# mcu.net
KiCad netlist of a schematic drawn in Altium Designer
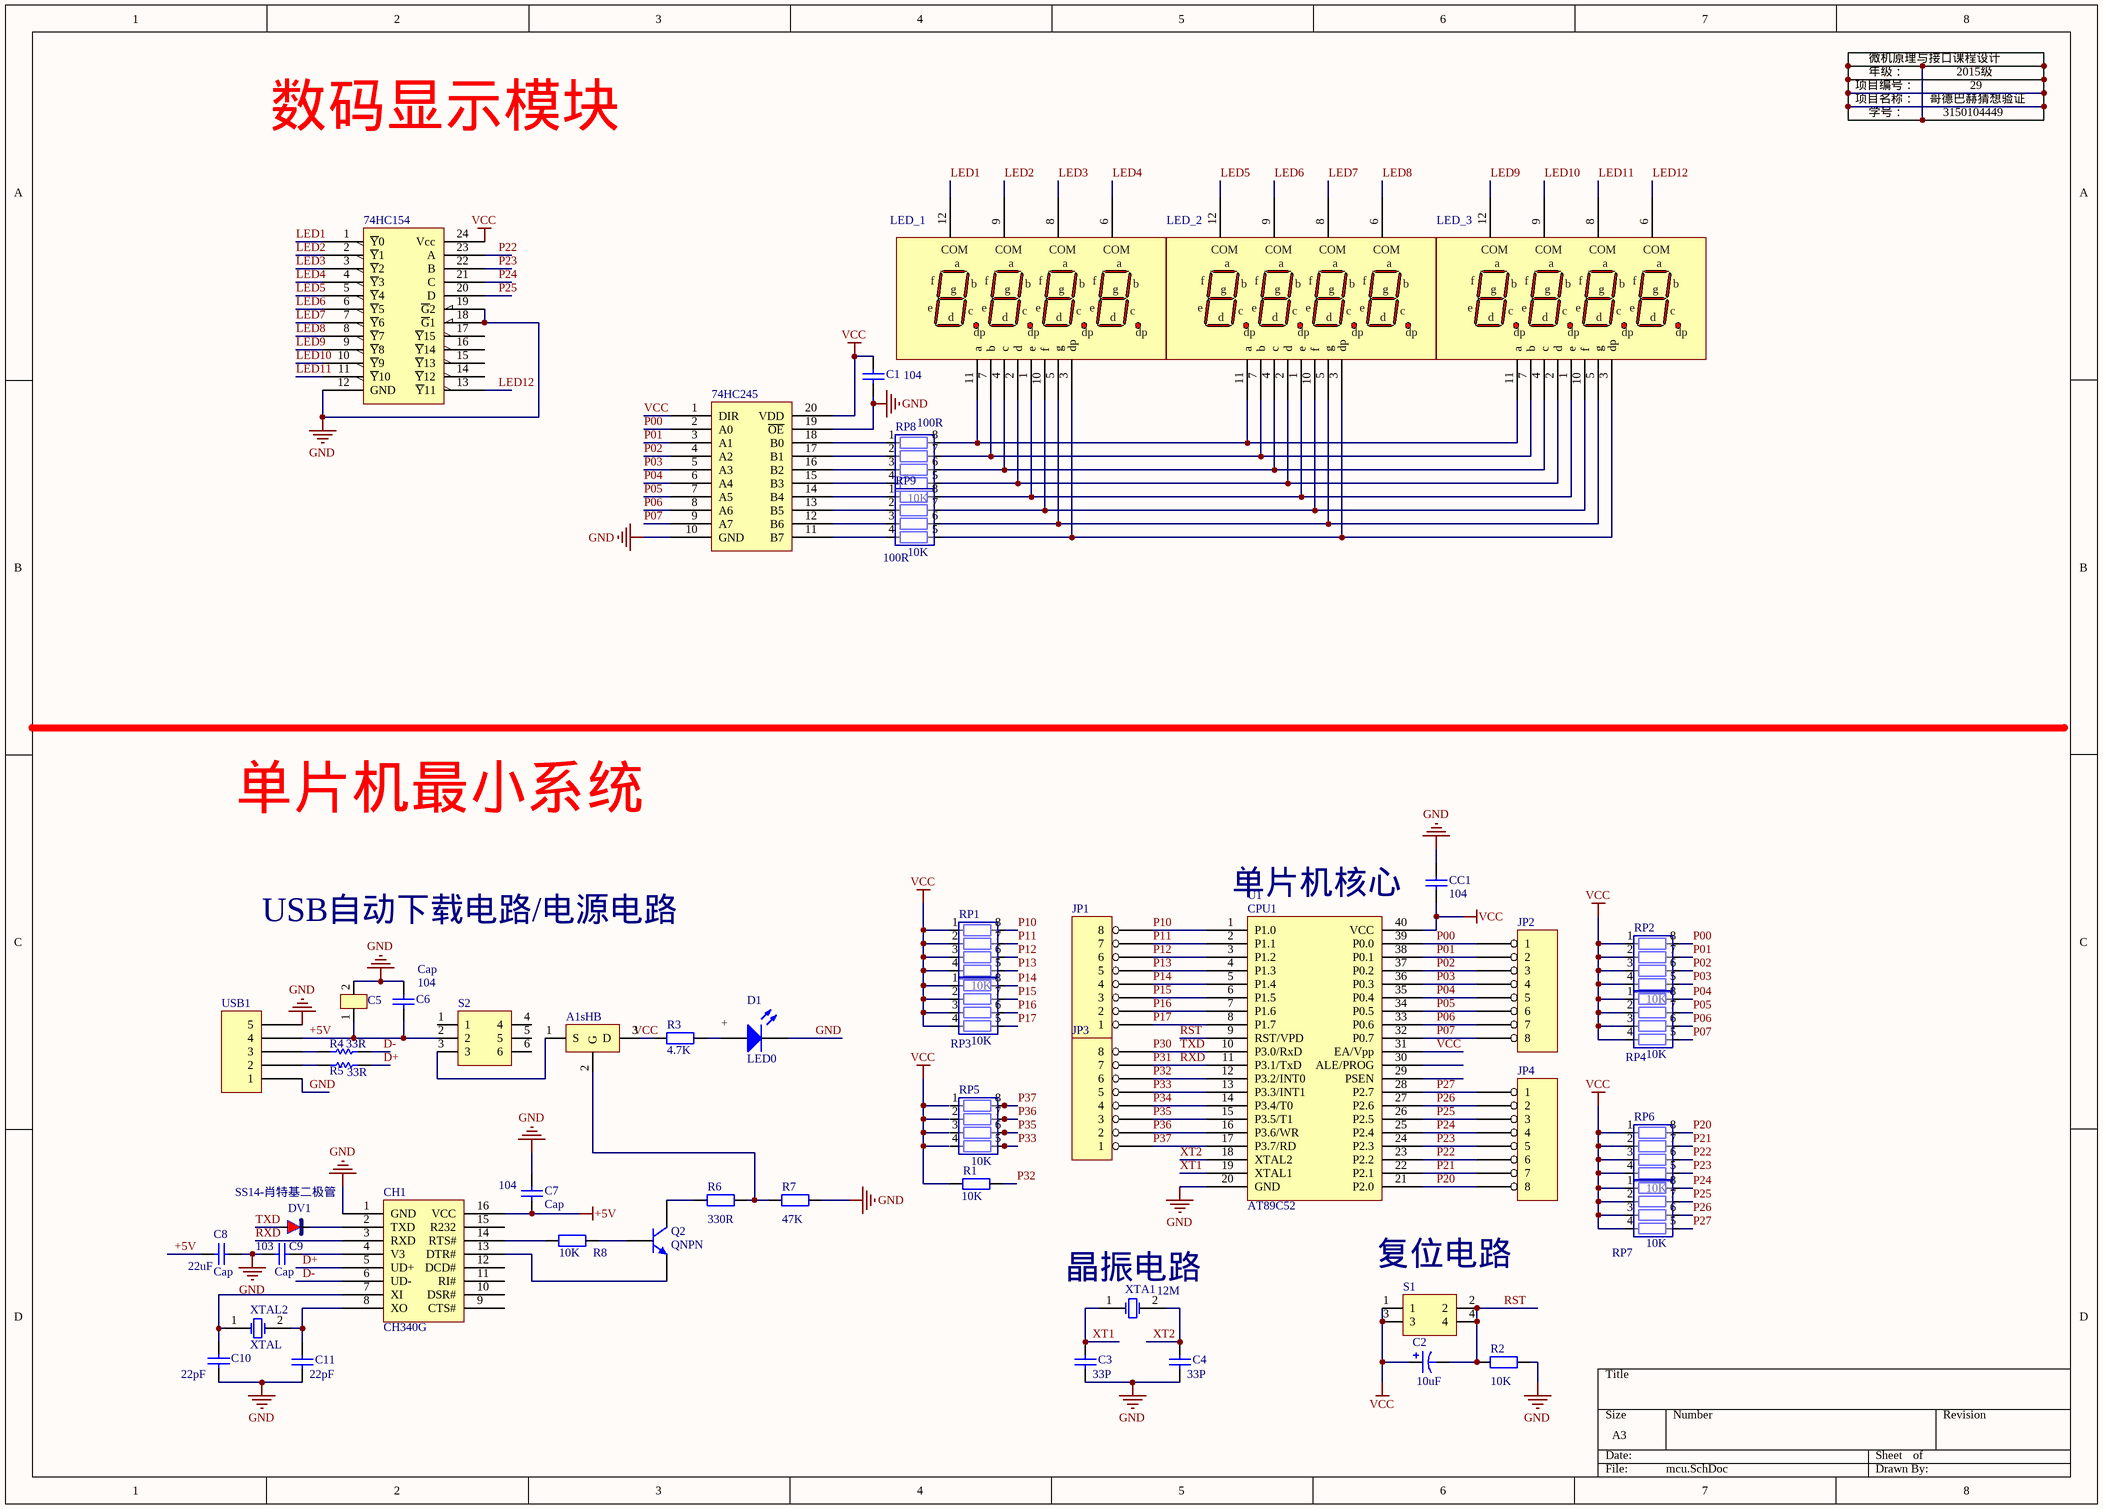
[diagram p0: mcu.SchDoc]

(export (version "E")
  (design (tool "Eeschema 10.0.6"))
  (components
    (comp (ref "74HC154")
      (value "74HC154")
      (footprint "mcu_PcbLib1:SOP24-74HC154D")
      (fields (field (name "PUBLISHER") "Altium Limited"))
      (libsource (lib "mcu_Schlib1") (part "74HC154"))
    )
    (comp (ref "74HC245")
      (value "74HC245")
      (footprint "mcu_PcbLib1:SOP20-74HC245")
      (fields (field (name "PUBLISHER") "Altium Limited"))
      (libsource (lib "mcu_Schlib1") (part "74HC245"))
    )
    (comp (ref "A1sHB")
      (value "A1sHB")
      (footprint "mcu_PcbLib1:A1sHB")
      (fields (field (name "PUBLISHER") "Altium Limited"))
      (libsource (lib "mcu_Schlib1") (part "A1sHB"))
    )
    (comp (ref "C1")
      (value "104")
      (footprint "RAD-0.3")
      (description "Capacitor")
      (fields (field (name "Comment") "Cap") (field (name "PUBLISHER") "Altium Limited"))
      (libsource (lib "Miscellaneous Devices") (part "Cap"))
    )
    (comp (ref "C2")
      (value "10uF")
      (footprint "RB7.6-15")
      (description "Polarized Capacitor (Radial)")
      (fields (field (name "Comment") "Cap Pol1") (field (name "PUBLISHER") "Altium Limited"))
      (libsource (lib "Miscellaneous Devices") (part "Cap Pol1"))
    )
    (comp (ref "C3")
      (value "33P")
      (footprint "RAD-0.3")
      (description "Capacitor")
      (fields (field (name "Comment") "Cap") (field (name "PUBLISHER") "Altium Limited"))
      (libsource (lib "Miscellaneous Devices") (part "Cap"))
    )
    (comp (ref "C4")
      (value "33P")
      (footprint "RAD-0.3")
      (description "Capacitor")
      (fields (field (name "Comment") "Cap") (field (name "PUBLISHER") "Altium Limited"))
      (libsource (lib "Miscellaneous Devices") (part "Cap"))
    )
    (comp (ref "C5")
      (value "470uF")
      (footprint "mcu_PcbLib1:C5-CP1")
      (description "High Conductance Fast Diode")
      (fields (field (name "PUBLISHER") "Altium Limited"))
      (libsource (lib "mcu_Schlib1") (part "C5"))
    )
    (comp (ref "C6")
      (value "Cap")
      (footprint "RAD-0.3")
      (description "Capacitor")
      (fields (field (name "ALTIUM_VALUE") "104") (field (name "PUBLISHER") "Altium Limited"))
      (libsource (lib "Miscellaneous Devices") (part "Cap"))
    )
    (comp (ref "C7")
      (value "Cap")
      (footprint "RAD-0.3")
      (description "Capacitor")
      (fields (field (name "ALTIUM_VALUE") "104") (field (name "PUBLISHER") "Altium Limited"))
      (libsource (lib "Miscellaneous Devices") (part "Cap"))
    )
    (comp (ref "C8")
      (value "Cap")
      (footprint "RAD-0.3")
      (description "Capacitor")
      (fields (field (name "ALTIUM_VALUE") "22uF") (field (name "PUBLISHER") "Altium Limited"))
      (libsource (lib "Miscellaneous Devices") (part "Cap"))
    )
    (comp (ref "C9")
      (value "Cap")
      (footprint "RAD-0.3")
      (description "Capacitor")
      (fields (field (name "ALTIUM_VALUE") "103") (field (name "PUBLISHER") "Altium Limited"))
      (libsource (lib "Miscellaneous Devices") (part "Cap"))
    )
    (comp (ref "C10")
      (value "22pF")
      (footprint "RAD-0.3")
      (description "Capacitor")
      (fields (field (name "Comment") "Cap") (field (name "PUBLISHER") "Altium Limited"))
      (libsource (lib "Miscellaneous Devices") (part "Cap"))
    )
    (comp (ref "C11")
      (value "22pF")
      (footprint "RAD-0.3")
      (description "Capacitor")
      (fields (field (name "Comment") "Cap") (field (name "PUBLISHER") "Altium Limited"))
      (libsource (lib "Miscellaneous Devices") (part "Cap"))
    )
    (comp (ref "CC1")
      (value "104")
      (footprint "RAD-0.3")
      (description "Capacitor")
      (fields (field (name "Comment") "Cap") (field (name "PUBLISHER") "Altium Limited"))
      (libsource (lib "Miscellaneous Devices") (part "Cap"))
    )
    (comp (ref "CH1")
      (value "CH340G")
      (footprint "mcu_PcbLib1:SOP16-CH1-CH340G")
      (description "CH1")
      (fields (field (name "PUBLISHER") "Altium Limited"))
      (libsource (lib "mcu_Schlib1") (part "CH1"))
    )
    (comp (ref "D1")
      (value "LED0")
      (footprint "LED-0")
      (description "Typical INFRARED GaAs LED")
      (fields (field (name "PUBLISHER") "Altium Limited"))
      (libsource (lib "Miscellaneous Devices") (part "LED0"))
    )
    (comp (ref "DV1")
      (value "SS14-肖特基二极管")
      (footprint "mcu_PcbLib1:DV1-SS14")
      (description "DV1")
      (fields (field (name "PUBLISHER") "Altium Limited"))
      (libsource (lib "mcu_Schlib1") (part "DV1"))
    )
    (comp (ref "JP1")
      (value "JP1")
      (footprint "mcu_PcbLib1:JP")
      (fields (field (name "PUBLISHER") "Altium Limited"))
      (libsource (lib "") (part "JP1_1"))
    )
    (comp (ref "JP2")
      (value "JP1")
      (footprint "mcu_PcbLib1:JP")
      (fields (field (name "PUBLISHER") "Altium Limited"))
      (libsource (lib "mcu_Schlib1") (part "JP1"))
    )
    (comp (ref "JP3")
      (value "JP1")
      (footprint "mcu_PcbLib1:JP")
      (fields (field (name "PUBLISHER") "Altium Limited"))
      (libsource (lib "") (part "JP1_1"))
    )
    (comp (ref "JP4")
      (value "JP1")
      (footprint "mcu_PcbLib1:JP")
      (fields (field (name "PUBLISHER") "Altium Limited"))
      (libsource (lib "mcu_Schlib1") (part "JP1"))
    )
    (comp (ref "LED_1")
      (value "LED_12")
      (footprint "mcu_PcbLib1:LED_12")
      (fields (field (name "PUBLISHER") "Altium Limited"))
      (libsource (lib "mcu_Schlib1") (part "LED_12"))
    )
    (comp (ref "LED_2")
      (value "LED_12")
      (footprint "mcu_PcbLib1:LED_12")
      (fields (field (name "PUBLISHER") "Altium Limited"))
      (libsource (lib "mcu_Schlib1") (part "LED_12"))
    )
    (comp (ref "LED_3")
      (value "LED_12")
      (footprint "mcu_PcbLib1:LED_12")
      (fields (field (name "PUBLISHER") "Altium Limited"))
      (libsource (lib "mcu_Schlib1") (part "LED_12"))
    )
    (comp (ref "Q2")
      (value "QNPN")
      (footprint "SOT-23B")
      (description "NPN Bipolar Transistor")
      (fields (field (name "PUBLISHER") "Altium Limited"))
      (libsource (lib "Miscellaneous Devices") (part "QNPN"))
    )
    (comp (ref "R1")
      (value "10K")
      (footprint "AXIAL-0.4")
      (description "Resistor")
      (fields (field (name "Comment") "Res2") (field (name "PUBLISHER") "Altium Limited"))
      (libsource (lib "Miscellaneous Devices") (part "Res2"))
    )
    (comp (ref "R2")
      (value "10K")
      (footprint "AXIAL-0.4")
      (description "Resistor")
      (fields (field (name "Comment") "Res2") (field (name "PUBLISHER") "Altium Limited"))
      (libsource (lib "Miscellaneous Devices") (part "Res2"))
    )
    (comp (ref "R3")
      (value "4.7K")
      (footprint "AXIAL-0.4")
      (description "Resistor")
      (fields (field (name "Comment") "Res2") (field (name "PUBLISHER") "Altium Limited"))
      (libsource (lib "Miscellaneous Devices") (part "Res2"))
    )
    (comp (ref "R4")
      (value "33R")
      (footprint "AXIAL-0.3")
      (description "Resistor")
      (fields (field (name "PUBLISHER") "Altium Limited"))
      (libsource (lib "Miscellaneous Devices") (part "Res1"))
    )
    (comp (ref "R5")
      (value "33R")
      (footprint "AXIAL-0.3")
      (description "Resistor")
      (fields (field (name "PUBLISHER") "Altium Limited"))
      (libsource (lib "Miscellaneous Devices") (part "Res1"))
    )
    (comp (ref "R6")
      (value "330R")
      (footprint "AXIAL-0.4")
      (description "Resistor")
      (fields (field (name "Comment") "Res2") (field (name "PUBLISHER") "Altium Limited"))
      (libsource (lib "Miscellaneous Devices") (part "Res2"))
    )
    (comp (ref "R7")
      (value "47K")
      (footprint "AXIAL-0.4")
      (description "Resistor")
      (fields (field (name "Comment") "Res2") (field (name "PUBLISHER") "Altium Limited"))
      (libsource (lib "Miscellaneous Devices") (part "Res2"))
    )
    (comp (ref "R8")
      (value "10K")
      (footprint "AXIAL-0.4")
      (description "Resistor")
      (fields (field (name "Comment") "Res2") (field (name "PUBLISHER") "Altium Limited"))
      (libsource (lib "Miscellaneous Devices") (part "Res2"))
    )
    (comp (ref "RP1")
      (value "RP1")
      (footprint "mcu_PcbLib1:RP-8P4R-0603")
      (fields (field (name "PUBLISHER") "Altium Limited"))
      (libsource (lib "mcu_Schlib1") (part "RP1"))
    )
    (comp (ref "RP2")
      (value "RP1")
      (footprint "mcu_PcbLib1:RP-8P4R-0603")
      (fields (field (name "PUBLISHER") "Altium Limited"))
      (libsource (lib "mcu_Schlib1") (part "RP1"))
    )
    (comp (ref "RP3")
      (value "RP1")
      (footprint "mcu_PcbLib1:RP-8P4R-0603")
      (fields (field (name "PUBLISHER") "Altium Limited"))
      (libsource (lib "mcu_Schlib1") (part "RP1"))
    )
    (comp (ref "RP4")
      (value "RP1")
      (footprint "mcu_PcbLib1:RP-8P4R-0603")
      (fields (field (name "PUBLISHER") "Altium Limited"))
      (libsource (lib "mcu_Schlib1") (part "RP1"))
    )
    (comp (ref "RP5")
      (value "RP1")
      (footprint "mcu_PcbLib1:RP-8P4R-0603")
      (fields (field (name "PUBLISHER") "Altium Limited"))
      (libsource (lib "mcu_Schlib1") (part "RP1"))
    )
    (comp (ref "RP6")
      (value "RP1")
      (footprint "mcu_PcbLib1:RP-8P4R-0603")
      (fields (field (name "PUBLISHER") "Altium Limited"))
      (libsource (lib "mcu_Schlib1") (part "RP1"))
    )
    (comp (ref "RP7")
      (value "RP1")
      (footprint "mcu_PcbLib1:RP-8P4R-0603")
      (fields (field (name "PUBLISHER") "Altium Limited"))
      (libsource (lib "mcu_Schlib1") (part "RP1"))
    )
    (comp (ref "RP8")
      (value "RP1")
      (footprint "mcu_PcbLib1:RP-8P4R-0603")
      (fields (field (name "PUBLISHER") "Altium Limited"))
      (libsource (lib "mcu_Schlib1") (part "RP1"))
    )
    (comp (ref "RP9")
      (value "RP1")
      (footprint "mcu_PcbLib1:RP-8P4R-0603")
      (fields (field (name "PUBLISHER") "Altium Limited"))
      (libsource (lib "mcu_Schlib1") (part "RP1"))
    )
    (comp (ref "S1")
      (value "S1")
      (footprint "mcu_PcbLib1:DIP4-S1")
      (fields (field (name "PUBLISHER") "Altium Limited"))
      (libsource (lib "mcu_Schlib1") (part "S1"))
    )
    (comp (ref "S2")
      (value "S2")
      (footprint "mcu_PcbLib1:DIP6-S2")
      (fields (field (name "PUBLISHER") "Altium Limited"))
      (libsource (lib "mcu_Schlib1") (part "S2"))
    )
    (comp (ref "U1")
      (value "AT89C52")
      (footprint "mcu_PcbLib1:CPU_DIP40")
      (fields (field (name "PUBLISHER") "Altium Limited"))
      (libsource (lib "mcu_Schlib1") (part "AT89C52"))
    )
    (comp (ref "USB1")
      (value "USB1")
      (footprint "mcu_PcbLib1:USB1")
      (fields (field (name "PUBLISHER") "Altium Limited"))
      (libsource (lib "mcu_Schlib1") (part "USB1"))
    )
    (comp (ref "XTA1")
      (value "12M")
      (footprint "R38")
      (description "Crystal Oscillator")
      (fields (field (name "PUBLISHER") "Altium Limited"))
      (libsource (lib "Miscellaneous Devices") (part "XTAL"))
    )
    (comp (ref "XTAL2")
      (value "XTAL")
      (footprint "R38")
      (description "Crystal Oscillator")
      (fields (field (name "PUBLISHER") "Altium Limited"))
      (libsource (lib "Miscellaneous Devices") (part "XTAL"))
    )
  )
  (nets
    (net (code "1") (name "+5V") (class "Default")
      (node (ref "C5") (pin "1") (pinfunction "1_1") (pintype "passive"))
      (node (ref "C6") (pin "1") (pinfunction "1_1") (pintype "passive"))
      (node (ref "C7") (pin "1") (pinfunction "1_1") (pintype "passive"))
      (node (ref "C8") (pin "1") (pinfunction "1_1") (pintype "passive"))
      (node (ref "CH1") (pin "16") (pinfunction "VCC_16") (pintype "passive"))
      (node (ref "S2") (pin "2") (pinfunction "2_2") (pintype "passive"))
      (node (ref "USB1") (pin "4") (pinfunction "4_4") (pintype "passive"))
    )
    (net (code "2") (name "/D+") (class "Default")
      (node (ref "CH1") (pin "5") (pinfunction "UD+_5") (pintype "passive"))
      (node (ref "R5") (pin "2") (pinfunction "2_2") (pintype "passive"))
    )
    (net (code "3") (name "/D-") (class "Default")
      (node (ref "CH1") (pin "6") (pinfunction "UD-_6") (pintype "passive"))
      (node (ref "R4") (pin "2") (pinfunction "2_2") (pintype "passive"))
    )
    (net (code "4") (name "/LED1") (class "Default")
      (node (ref "74HC154") (pin "1") (pinfunction "~{Y}0_1") (pintype "passive"))
      (node (ref "LED_1") (pin "12") (pinfunction "COM_12") (pintype "passive"))
    )
    (net (code "5") (name "/LED2") (class "Default")
      (node (ref "74HC154") (pin "2") (pinfunction "~{Y}1_2") (pintype "passive"))
      (node (ref "LED_1") (pin "9") (pinfunction "COM_9") (pintype "passive"))
    )
    (net (code "6") (name "/LED3") (class "Default")
      (node (ref "74HC154") (pin "3") (pinfunction "~{Y}2_3") (pintype "passive"))
      (node (ref "LED_1") (pin "8") (pinfunction "COM_8") (pintype "passive"))
    )
    (net (code "7") (name "/LED4") (class "Default")
      (node (ref "74HC154") (pin "4") (pinfunction "~{Y}3_4") (pintype "passive"))
      (node (ref "LED_1") (pin "6") (pinfunction "COM_6") (pintype "passive"))
    )
    (net (code "8") (name "/LED5") (class "Default")
      (node (ref "74HC154") (pin "5") (pinfunction "~{Y}4_5") (pintype "passive"))
      (node (ref "LED_2") (pin "12") (pinfunction "COM_12") (pintype "passive"))
    )
    (net (code "9") (name "/LED6") (class "Default")
      (node (ref "74HC154") (pin "6") (pinfunction "~{Y}5_6") (pintype "passive"))
      (node (ref "LED_2") (pin "9") (pinfunction "COM_9") (pintype "passive"))
    )
    (net (code "10") (name "/LED7") (class "Default")
      (node (ref "74HC154") (pin "7") (pinfunction "~{Y}6_7") (pintype "passive"))
      (node (ref "LED_2") (pin "8") (pinfunction "COM_8") (pintype "passive"))
    )
    (net (code "11") (name "/LED8") (class "Default")
      (node (ref "74HC154") (pin "8") (pinfunction "~{Y}7_8") (pintype "passive"))
      (node (ref "LED_2") (pin "6") (pinfunction "COM_6") (pintype "passive"))
    )
    (net (code "12") (name "/LED9") (class "Default")
      (node (ref "74HC154") (pin "9") (pinfunction "~{Y}8_9") (pintype "passive"))
      (node (ref "LED_3") (pin "12") (pinfunction "COM_12") (pintype "passive"))
    )
    (net (code "13") (name "/LED10") (class "Default")
      (node (ref "74HC154") (pin "10") (pinfunction "~{Y}9_10") (pintype "passive"))
      (node (ref "LED_3") (pin "9") (pinfunction "COM_9") (pintype "passive"))
    )
    (net (code "14") (name "/LED11") (class "Default")
      (node (ref "74HC154") (pin "11") (pinfunction "~{Y}10_11") (pintype "passive"))
      (node (ref "LED_3") (pin "8") (pinfunction "COM_8") (pintype "passive"))
    )
    (net (code "15") (name "/LED12") (class "Default")
      (node (ref "74HC154") (pin "13") (pinfunction "~{Y}11_13") (pintype "passive"))
      (node (ref "LED_3") (pin "6") (pinfunction "COM_6") (pintype "passive"))
    )
    (net (code "16") (name "/P00") (class "Default")
      (node (ref "74HC245") (pin "2") (pinfunction "A0_2") (pintype "passive"))
      (node (ref "JP2") (pin "1") (pinfunction "1_1") (pintype "passive"))
      (node (ref "RP2") (pin "8") (pinfunction "8_8") (pintype "passive"))
      (node (ref "U1") (pin "39") (pinfunction "P0.0_39") (pintype "passive"))
    )
    (net (code "17") (name "/P01") (class "Default")
      (node (ref "74HC245") (pin "3") (pinfunction "A1_3") (pintype "passive"))
      (node (ref "JP2") (pin "2") (pinfunction "2_2") (pintype "passive"))
      (node (ref "RP2") (pin "7") (pinfunction "7_7") (pintype "passive"))
      (node (ref "U1") (pin "38") (pinfunction "P0.1_38") (pintype "passive"))
    )
    (net (code "18") (name "/P02") (class "Default")
      (node (ref "74HC245") (pin "4") (pinfunction "A2_4") (pintype "passive"))
      (node (ref "JP2") (pin "3") (pinfunction "3_3") (pintype "passive"))
      (node (ref "RP2") (pin "6") (pinfunction "6_6") (pintype "passive"))
      (node (ref "U1") (pin "37") (pinfunction "P0.2_37") (pintype "passive"))
    )
    (net (code "19") (name "/P03") (class "Default")
      (node (ref "74HC245") (pin "5") (pinfunction "A3_5") (pintype "passive"))
      (node (ref "JP2") (pin "4") (pinfunction "4_4") (pintype "passive"))
      (node (ref "RP2") (pin "5") (pinfunction "5_5") (pintype "passive"))
      (node (ref "U1") (pin "36") (pinfunction "P0.3_36") (pintype "passive"))
    )
    (net (code "20") (name "/P04") (class "Default")
      (node (ref "74HC245") (pin "6") (pinfunction "A4_6") (pintype "passive"))
      (node (ref "JP2") (pin "5") (pinfunction "5_5") (pintype "passive"))
      (node (ref "RP4") (pin "8") (pinfunction "8_8") (pintype "passive"))
      (node (ref "U1") (pin "35") (pinfunction "P0.4_35") (pintype "passive"))
    )
    (net (code "21") (name "/P05") (class "Default")
      (node (ref "74HC245") (pin "7") (pinfunction "A5_7") (pintype "passive"))
      (node (ref "JP2") (pin "6") (pinfunction "6_6") (pintype "passive"))
      (node (ref "RP4") (pin "7") (pinfunction "7_7") (pintype "passive"))
      (node (ref "U1") (pin "34") (pinfunction "P0.5_34") (pintype "passive"))
    )
    (net (code "22") (name "/P06") (class "Default")
      (node (ref "74HC245") (pin "8") (pinfunction "A6_8") (pintype "passive"))
      (node (ref "JP2") (pin "7") (pinfunction "7_7") (pintype "passive"))
      (node (ref "RP4") (pin "6") (pinfunction "6_6") (pintype "passive"))
      (node (ref "U1") (pin "33") (pinfunction "P0.6_33") (pintype "passive"))
    )
    (net (code "23") (name "/P07") (class "Default")
      (node (ref "74HC245") (pin "9") (pinfunction "A7_9") (pintype "passive"))
      (node (ref "JP2") (pin "8") (pinfunction "8_8") (pintype "passive"))
      (node (ref "RP4") (pin "5") (pinfunction "5_5") (pintype "passive"))
      (node (ref "U1") (pin "32") (pinfunction "P0.7_32") (pintype "passive"))
    )
    (net (code "24") (name "/P10") (class "Default")
      (node (ref "JP1") (pin "8") (pinfunction "8_8") (pintype "passive"))
      (node (ref "RP1") (pin "8") (pinfunction "8_8") (pintype "passive"))
      (node (ref "U1") (pin "1") (pinfunction "P1.0_1") (pintype "passive"))
    )
    (net (code "25") (name "/P11") (class "Default")
      (node (ref "JP1") (pin "7") (pinfunction "7_7") (pintype "passive"))
      (node (ref "RP1") (pin "7") (pinfunction "7_7") (pintype "passive"))
      (node (ref "U1") (pin "2") (pinfunction "P1.1_2") (pintype "passive"))
    )
    (net (code "26") (name "/P12") (class "Default")
      (node (ref "JP1") (pin "6") (pinfunction "6_6") (pintype "passive"))
      (node (ref "RP1") (pin "6") (pinfunction "6_6") (pintype "passive"))
      (node (ref "U1") (pin "3") (pinfunction "P1.2_3") (pintype "passive"))
    )
    (net (code "27") (name "/P13") (class "Default")
      (node (ref "JP1") (pin "5") (pinfunction "5_5") (pintype "passive"))
      (node (ref "RP1") (pin "5") (pinfunction "5_5") (pintype "passive"))
      (node (ref "U1") (pin "4") (pinfunction "P1.3_4") (pintype "passive"))
    )
    (net (code "28") (name "/P14") (class "Default")
      (node (ref "JP1") (pin "4") (pinfunction "4_4") (pintype "passive"))
      (node (ref "RP3") (pin "8") (pinfunction "8_8") (pintype "passive"))
      (node (ref "U1") (pin "5") (pinfunction "P1.4_5") (pintype "passive"))
    )
    (net (code "29") (name "/P15") (class "Default")
      (node (ref "JP1") (pin "3") (pinfunction "3_3") (pintype "passive"))
      (node (ref "RP3") (pin "7") (pinfunction "7_7") (pintype "passive"))
      (node (ref "U1") (pin "6") (pinfunction "P1.5_6") (pintype "passive"))
    )
    (net (code "30") (name "/P16") (class "Default")
      (node (ref "JP1") (pin "2") (pinfunction "2_2") (pintype "passive"))
      (node (ref "RP3") (pin "6") (pinfunction "6_6") (pintype "passive"))
      (node (ref "U1") (pin "7") (pinfunction "P1.6_7") (pintype "passive"))
    )
    (net (code "31") (name "/P17") (class "Default")
      (node (ref "JP1") (pin "1") (pinfunction "1_1") (pintype "passive"))
      (node (ref "RP3") (pin "5") (pinfunction "5_5") (pintype "passive"))
      (node (ref "U1") (pin "8") (pinfunction "P1.7_8") (pintype "passive"))
    )
    (net (code "32") (name "/P20") (class "Default")
      (node (ref "JP4") (pin "8") (pinfunction "8_8") (pintype "passive"))
      (node (ref "RP6") (pin "8") (pinfunction "8_8") (pintype "passive"))
      (node (ref "U1") (pin "21") (pinfunction "P2.0_21") (pintype "passive"))
    )
    (net (code "33") (name "/P21") (class "Default")
      (node (ref "JP4") (pin "7") (pinfunction "7_7") (pintype "passive"))
      (node (ref "RP6") (pin "7") (pinfunction "7_7") (pintype "passive"))
      (node (ref "U1") (pin "22") (pinfunction "P2.1_22") (pintype "passive"))
    )
    (net (code "34") (name "/P22") (class "Default")
      (node (ref "74HC154") (pin "23") (pinfunction "A_23") (pintype "passive"))
      (node (ref "JP4") (pin "6") (pinfunction "6_6") (pintype "passive"))
      (node (ref "RP6") (pin "6") (pinfunction "6_6") (pintype "passive"))
      (node (ref "U1") (pin "23") (pinfunction "P2.2_23") (pintype "passive"))
    )
    (net (code "35") (name "/P23") (class "Default")
      (node (ref "74HC154") (pin "22") (pinfunction "B_22") (pintype "passive"))
      (node (ref "JP4") (pin "5") (pinfunction "5_5") (pintype "passive"))
      (node (ref "RP6") (pin "5") (pinfunction "5_5") (pintype "passive"))
      (node (ref "U1") (pin "24") (pinfunction "P2.3_24") (pintype "passive"))
    )
    (net (code "36") (name "/P24") (class "Default")
      (node (ref "74HC154") (pin "21") (pinfunction "C_21") (pintype "passive"))
      (node (ref "JP4") (pin "4") (pinfunction "4_4") (pintype "passive"))
      (node (ref "RP7") (pin "8") (pinfunction "8_8") (pintype "passive"))
      (node (ref "U1") (pin "25") (pinfunction "P2.4_25") (pintype "passive"))
    )
    (net (code "37") (name "/P25") (class "Default")
      (node (ref "74HC154") (pin "20") (pinfunction "D_20") (pintype "passive"))
      (node (ref "JP4") (pin "3") (pinfunction "3_3") (pintype "passive"))
      (node (ref "RP7") (pin "7") (pinfunction "7_7") (pintype "passive"))
      (node (ref "U1") (pin "26") (pinfunction "P2.5_26") (pintype "passive"))
    )
    (net (code "38") (name "/P26") (class "Default")
      (node (ref "JP4") (pin "2") (pinfunction "2_2") (pintype "passive"))
      (node (ref "RP7") (pin "6") (pinfunction "6_6") (pintype "passive"))
      (node (ref "U1") (pin "27") (pinfunction "P2.6_27") (pintype "passive"))
    )
    (net (code "39") (name "/P27") (class "Default")
      (node (ref "JP4") (pin "1") (pinfunction "1_1") (pintype "passive"))
      (node (ref "RP7") (pin "5") (pinfunction "5_5") (pintype "passive"))
      (node (ref "U1") (pin "28") (pinfunction "P2.7_28") (pintype "passive"))
    )
    (net (code "40") (name "/P30") (class "Default")
      (node (ref "DV1") (pin "1") (pinfunction "1_1") (pintype "passive"))
      (node (ref "JP3") (pin "8") (pinfunction "8_8") (pintype "passive"))
      (node (ref "U1") (pin "10") (pinfunction "P3.0/RxD_10") (pintype "passive"))
    )
    (net (code "41") (name "/P31") (class "Default")
      (node (ref "CH1") (pin "3") (pinfunction "RXD_3") (pintype "passive"))
      (node (ref "JP3") (pin "7") (pinfunction "7_7") (pintype "passive"))
      (node (ref "U1") (pin "11") (pinfunction "P3.1/TxD_11") (pintype "passive"))
    )
    (net (code "42") (name "/P32") (class "Default")
      (node (ref "JP3") (pin "6") (pinfunction "6_6") (pintype "passive"))
      (node (ref "R1") (pin "2") (pinfunction "2_2") (pintype "passive"))
      (node (ref "U1") (pin "12") (pinfunction "P3.2/INT0_12") (pintype "passive"))
    )
    (net (code "43") (name "/P33") (class "Default")
      (node (ref "JP3") (pin "5") (pinfunction "5_5") (pintype "passive"))
      (node (ref "RP5") (pin "5") (pinfunction "5_5") (pintype "passive"))
      (node (ref "U1") (pin "13") (pinfunction "P3.3/INT1_13") (pintype "passive"))
    )
    (net (code "44") (name "/P34") (class "Default")
      (node (ref "JP3") (pin "4") (pinfunction "4_4") (pintype "passive"))
      (node (ref "U1") (pin "14") (pinfunction "P3.4/T0_14") (pintype "passive"))
    )
    (net (code "45") (name "/P35") (class "Default")
      (node (ref "JP3") (pin "3") (pinfunction "3_3") (pintype "passive"))
      (node (ref "RP5") (pin "6") (pinfunction "6_6") (pintype "passive"))
      (node (ref "U1") (pin "15") (pinfunction "P3.5/T1_15") (pintype "passive"))
    )
    (net (code "46") (name "/P36") (class "Default")
      (node (ref "JP3") (pin "2") (pinfunction "2_2") (pintype "passive"))
      (node (ref "RP5") (pin "7") (pinfunction "7_7") (pintype "passive"))
      (node (ref "U1") (pin "16") (pinfunction "P3.6/WR_16") (pintype "passive"))
    )
    (net (code "47") (name "/P37") (class "Default")
      (node (ref "JP3") (pin "1") (pinfunction "1_1") (pintype "passive"))
      (node (ref "RP5") (pin "8") (pinfunction "8_8") (pintype "passive"))
      (node (ref "U1") (pin "17") (pinfunction "P3.7/RD_17") (pintype "passive"))
    )
    (net (code "48") (name "/RST") (class "Default")
      (node (ref "C2") (pin "2") (pinfunction "2_2") (pintype "passive"))
      (node (ref "R2") (pin "1") (pinfunction "1_1") (pintype "passive"))
      (node (ref "S1") (pin "2") (pinfunction "2_2") (pintype "passive"))
      (node (ref "S1") (pin "4") (pinfunction "4_4") (pintype "passive"))
      (node (ref "U1") (pin "9") (pinfunction "RST/VPD_9") (pintype "passive"))
    )
    (net (code "49") (name "/XT1") (class "Default")
      (node (ref "C3") (pin "2") (pinfunction "2_2") (pintype "passive"))
      (node (ref "U1") (pin "19") (pinfunction "XTAL1_19") (pintype "passive"))
      (node (ref "XTA1") (pin "1") (pinfunction "OSC1_1") (pintype "passive"))
    )
    (net (code "50") (name "/XT2") (class "Default")
      (node (ref "C4") (pin "2") (pinfunction "2_2") (pintype "passive"))
      (node (ref "U1") (pin "18") (pinfunction "XTAL2_18") (pintype "passive"))
      (node (ref "XTA1") (pin "2") (pinfunction "OSC2_2") (pintype "passive"))
    )
    (net (code "51") (name "GND") (class "Default")
      (node (ref "74HC154") (pin "12") (pinfunction "GND_12") (pintype "passive"))
      (node (ref "74HC154") (pin "18") (pinfunction "~{G}1_18") (pintype "passive"))
      (node (ref "74HC154") (pin "19") (pinfunction "~{G}2_19") (pintype "passive"))
      (node (ref "74HC245") (pin "10") (pinfunction "GND_10") (pintype "passive"))
      (node (ref "74HC245") (pin "19") (pinfunction "~{OE}_19") (pintype "passive"))
      (node (ref "C1") (pin "1") (pinfunction "1_1") (pintype "passive"))
      (node (ref "C10") (pin "1") (pinfunction "1_1") (pintype "passive"))
      (node (ref "C11") (pin "1") (pinfunction "1_1") (pintype "passive"))
      (node (ref "C3") (pin "1") (pinfunction "1_1") (pintype "passive"))
      (node (ref "C4") (pin "1") (pinfunction "1_1") (pintype "passive"))
      (node (ref "C5") (pin "2") (pinfunction "2_2") (pintype "passive"))
      (node (ref "C6") (pin "2") (pinfunction "2_2") (pintype "passive"))
      (node (ref "C7") (pin "2") (pinfunction "2_2") (pintype "passive"))
      (node (ref "C8") (pin "2") (pinfunction "2_2") (pintype "passive"))
      (node (ref "C9") (pin "1") (pinfunction "1_1") (pintype "passive"))
      (node (ref "CC1") (pin "2") (pinfunction "2_2") (pintype "passive"))
      (node (ref "CH1") (pin "1") (pinfunction "GND_1") (pintype "passive"))
      (node (ref "D1") (pin "2") (pinfunction "K_2") (pintype "passive"))
      (node (ref "R2") (pin "2") (pinfunction "2_2") (pintype "passive"))
      (node (ref "R7") (pin "2") (pinfunction "2_2") (pintype "passive"))
      (node (ref "U1") (pin "20") (pinfunction "GND_20") (pintype "passive"))
      (node (ref "USB1") (pin "1") (pinfunction "1_1") (pintype "passive"))
      (node (ref "USB1") (pin "5") (pinfunction "5_5") (pintype "passive"))
    )
    (net (code "52") (name "Net-(74HC245-B0)") (class "Default")
      (node (ref "74HC245") (pin "18") (pinfunction "B0_18") (pintype "passive"))
      (node (ref "RP8") (pin "1") (pinfunction "1_1") (pintype "passive"))
    )
    (net (code "53") (name "Net-(74HC245-B1)") (class "Default")
      (node (ref "74HC245") (pin "17") (pinfunction "B1_17") (pintype "passive"))
      (node (ref "RP8") (pin "2") (pinfunction "2_2") (pintype "passive"))
    )
    (net (code "54") (name "Net-(74HC245-B2)") (class "Default")
      (node (ref "74HC245") (pin "16") (pinfunction "B2_16") (pintype "passive"))
      (node (ref "RP8") (pin "3") (pinfunction "3_3") (pintype "passive"))
    )
    (net (code "55") (name "Net-(74HC245-B3)") (class "Default")
      (node (ref "74HC245") (pin "15") (pinfunction "B3_15") (pintype "passive"))
      (node (ref "RP8") (pin "4") (pinfunction "4_4") (pintype "passive"))
    )
    (net (code "56") (name "Net-(74HC245-B4)") (class "Default")
      (node (ref "74HC245") (pin "14") (pinfunction "B4_14") (pintype "passive"))
      (node (ref "RP9") (pin "1") (pinfunction "1_1") (pintype "passive"))
    )
    (net (code "57") (name "Net-(74HC245-B5)") (class "Default")
      (node (ref "74HC245") (pin "13") (pinfunction "B5_13") (pintype "passive"))
      (node (ref "RP9") (pin "2") (pinfunction "2_2") (pintype "passive"))
    )
    (net (code "58") (name "Net-(74HC245-B6)") (class "Default")
      (node (ref "74HC245") (pin "12") (pinfunction "B6_12") (pintype "passive"))
      (node (ref "RP9") (pin "3") (pinfunction "3_3") (pintype "passive"))
    )
    (net (code "59") (name "Net-(74HC245-B7)") (class "Default")
      (node (ref "74HC245") (pin "11") (pinfunction "B7_11") (pintype "passive"))
      (node (ref "RP9") (pin "4") (pinfunction "4_4") (pintype "passive"))
    )
    (net (code "60") (name "Net-(A1sHB-D)") (class "Default")
      (node (ref "A1sHB") (pin "3") (pinfunction "D_3") (pintype "passive"))
      (node (ref "R3") (pin "1") (pinfunction "1_1") (pintype "passive"))
    )
    (net (code "61") (name "Net-(A1sHB-G)") (class "Default")
      (node (ref "A1sHB") (pin "2") (pinfunction "G_2") (pintype "passive"))
      (node (ref "R6") (pin "2") (pinfunction "2_2") (pintype "passive"))
      (node (ref "R7") (pin "1") (pinfunction "1_1") (pintype "passive"))
    )
    (net (code "62") (name "Net-(A1sHB-S)") (class "Default")
      (node (ref "A1sHB") (pin "1") (pinfunction "S_1") (pintype "passive"))
      (node (ref "S2") (pin "3") (pinfunction "3_3") (pintype "passive"))
    )
    (net (code "63") (name "Net-(CH1-DTR#)") (class "Default")
      (node (ref "CH1") (pin "13") (pinfunction "DTR#_13") (pintype "passive"))
      (node (ref "Q2") (pin "3") (pinfunction "E_3") (pintype "passive"))
    )
    (net (code "64") (name "Net-(CH1-RTS#)") (class "Default")
      (node (ref "CH1") (pin "14") (pinfunction "RTS#_14") (pintype "passive"))
      (node (ref "R8") (pin "1") (pinfunction "1_1") (pintype "passive"))
    )
    (net (code "65") (name "Net-(CH1-TXD)") (class "Default")
      (node (ref "CH1") (pin "2") (pinfunction "TXD_2") (pintype "passive"))
      (node (ref "DV1") (pin "2") (pinfunction "2_2") (pintype "passive"))
    )
    (net (code "66") (name "Net-(CH1-V3)") (class "Default")
      (node (ref "C9") (pin "2") (pinfunction "2_2") (pintype "passive"))
      (node (ref "CH1") (pin "4") (pinfunction "V3_4") (pintype "passive"))
    )
    (net (code "67") (name "Net-(CH1-XI)") (class "Default")
      (node (ref "C10") (pin "2") (pinfunction "2_2") (pintype "passive"))
      (node (ref "CH1") (pin "7") (pinfunction "XI_7") (pintype "passive"))
      (node (ref "XTAL2") (pin "1") (pinfunction "OSC1_1") (pintype "passive"))
    )
    (net (code "68") (name "Net-(CH1-XO)") (class "Default")
      (node (ref "C11") (pin "2") (pinfunction "2_2") (pintype "passive"))
      (node (ref "CH1") (pin "8") (pinfunction "XO_8") (pintype "passive"))
      (node (ref "XTAL2") (pin "2") (pinfunction "OSC2_2") (pintype "passive"))
    )
    (net (code "69") (name "Net-(D1-A)") (class "Default")
      (node (ref "D1") (pin "1") (pinfunction "A_1") (pintype "passive"))
      (node (ref "R3") (pin "2") (pinfunction "2_2") (pintype "passive"))
    )
    (net (code "70") (name "Net-(LED_1-a)") (class "Default")
      (node (ref "LED_1") (pin "11") (pinfunction "a_11") (pintype "passive"))
      (node (ref "LED_2") (pin "11") (pinfunction "a_11") (pintype "passive"))
      (node (ref "LED_3") (pin "11") (pinfunction "a_11") (pintype "passive"))
      (node (ref "RP8") (pin "8") (pinfunction "8_8") (pintype "passive"))
    )
    (net (code "71") (name "Net-(LED_1-b)") (class "Default")
      (node (ref "LED_1") (pin "7") (pinfunction "b_7") (pintype "passive"))
      (node (ref "LED_2") (pin "7") (pinfunction "b_7") (pintype "passive"))
      (node (ref "LED_3") (pin "7") (pinfunction "b_7") (pintype "passive"))
      (node (ref "RP8") (pin "7") (pinfunction "7_7") (pintype "passive"))
    )
    (net (code "72") (name "Net-(LED_1-c)") (class "Default")
      (node (ref "LED_1") (pin "4") (pinfunction "c_4") (pintype "passive"))
      (node (ref "LED_2") (pin "4") (pinfunction "c_4") (pintype "passive"))
      (node (ref "LED_3") (pin "4") (pinfunction "c_4") (pintype "passive"))
      (node (ref "RP8") (pin "6") (pinfunction "6_6") (pintype "passive"))
    )
    (net (code "73") (name "Net-(LED_1-d)") (class "Default")
      (node (ref "LED_1") (pin "2") (pinfunction "d_2") (pintype "passive"))
      (node (ref "LED_2") (pin "2") (pinfunction "d_2") (pintype "passive"))
      (node (ref "LED_3") (pin "2") (pinfunction "d_2") (pintype "passive"))
      (node (ref "RP8") (pin "5") (pinfunction "5_5") (pintype "passive"))
    )
    (net (code "74") (name "Net-(LED_1-dp)") (class "Default")
      (node (ref "LED_1") (pin "3") (pinfunction "dp_3") (pintype "passive"))
      (node (ref "LED_2") (pin "3") (pinfunction "dp_3") (pintype "passive"))
      (node (ref "LED_3") (pin "3") (pinfunction "dp_3") (pintype "passive"))
      (node (ref "RP9") (pin "5") (pinfunction "5_5") (pintype "passive"))
    )
    (net (code "75") (name "Net-(LED_1-e)") (class "Default")
      (node (ref "LED_1") (pin "1") (pinfunction "e_1") (pintype "passive"))
      (node (ref "LED_2") (pin "1") (pinfunction "e_1") (pintype "passive"))
      (node (ref "LED_3") (pin "1") (pinfunction "e_1") (pintype "passive"))
      (node (ref "RP9") (pin "8") (pinfunction "8_8") (pintype "passive"))
    )
    (net (code "76") (name "Net-(LED_1-f)") (class "Default")
      (node (ref "LED_1") (pin "10") (pinfunction "f_10") (pintype "passive"))
      (node (ref "LED_2") (pin "10") (pinfunction "f_10") (pintype "passive"))
      (node (ref "LED_3") (pin "10") (pinfunction "f_10") (pintype "passive"))
      (node (ref "RP9") (pin "7") (pinfunction "7_7") (pintype "passive"))
    )
    (net (code "77") (name "Net-(LED_1-g)") (class "Default")
      (node (ref "LED_1") (pin "5") (pinfunction "g_5") (pintype "passive"))
      (node (ref "LED_2") (pin "5") (pinfunction "g_5") (pintype "passive"))
      (node (ref "LED_3") (pin "5") (pinfunction "g_5") (pintype "passive"))
      (node (ref "RP9") (pin "6") (pinfunction "6_6") (pintype "passive"))
    )
    (net (code "78") (name "Net-(Q2-B)") (class "Default")
      (node (ref "Q2") (pin "2") (pinfunction "B_2") (pintype "passive"))
      (node (ref "R8") (pin "2") (pinfunction "2_2") (pintype "passive"))
    )
    (net (code "79") (name "Net-(Q2-C)") (class "Default")
      (node (ref "Q2") (pin "1") (pinfunction "C_1") (pintype "passive"))
      (node (ref "R6") (pin "1") (pinfunction "1_1") (pintype "passive"))
    )
    (net (code "80") (name "Net-(R4-Pad1)") (class "Default")
      (node (ref "R4") (pin "1") (pinfunction "1_1") (pintype "passive"))
      (node (ref "USB1") (pin "3") (pinfunction "3_3") (pintype "passive"))
    )
    (net (code "81") (name "Net-(R5-Pad1)") (class "Default")
      (node (ref "R5") (pin "1") (pinfunction "1_1") (pintype "passive"))
      (node (ref "USB1") (pin "2") (pinfunction "2_2") (pintype "passive"))
    )
    (net (code "82") (name "VCC") (class "Default")
      (node (ref "74HC154") (pin "24") (pinfunction "Vcc_24") (pintype "passive"))
      (node (ref "74HC245") (pin "1") (pinfunction "DIR_1") (pintype "passive"))
      (node (ref "74HC245") (pin "20") (pinfunction "VDD_20") (pintype "passive"))
      (node (ref "C1") (pin "2") (pinfunction "2_2") (pintype "passive"))
      (node (ref "C2") (pin "1") (pinfunction "1_1") (pintype "passive"))
      (node (ref "CC1") (pin "1") (pinfunction "1_1") (pintype "passive"))
      (node (ref "R1") (pin "1") (pinfunction "1_1") (pintype "passive"))
      (node (ref "RP1") (pin "1") (pinfunction "1_1") (pintype "passive"))
      (node (ref "RP1") (pin "2") (pinfunction "2_2") (pintype "passive"))
      (node (ref "RP1") (pin "3") (pinfunction "3_3") (pintype "passive"))
      (node (ref "RP1") (pin "4") (pinfunction "4_4") (pintype "passive"))
      (node (ref "RP2") (pin "1") (pinfunction "1_1") (pintype "passive"))
      (node (ref "RP2") (pin "2") (pinfunction "2_2") (pintype "passive"))
      (node (ref "RP2") (pin "3") (pinfunction "3_3") (pintype "passive"))
      (node (ref "RP2") (pin "4") (pinfunction "4_4") (pintype "passive"))
      (node (ref "RP3") (pin "1") (pinfunction "1_1") (pintype "passive"))
      (node (ref "RP3") (pin "2") (pinfunction "2_2") (pintype "passive"))
      (node (ref "RP3") (pin "3") (pinfunction "3_3") (pintype "passive"))
      (node (ref "RP3") (pin "4") (pinfunction "4_4") (pintype "passive"))
      (node (ref "RP4") (pin "1") (pinfunction "1_1") (pintype "passive"))
      (node (ref "RP4") (pin "2") (pinfunction "2_2") (pintype "passive"))
      (node (ref "RP4") (pin "3") (pinfunction "3_3") (pintype "passive"))
      (node (ref "RP4") (pin "4") (pinfunction "4_4") (pintype "passive"))
      (node (ref "RP6") (pin "1") (pinfunction "1_1") (pintype "passive"))
      (node (ref "RP6") (pin "2") (pinfunction "2_2") (pintype "passive"))
      (node (ref "RP6") (pin "3") (pinfunction "3_3") (pintype "passive"))
      (node (ref "RP6") (pin "4") (pinfunction "4_4") (pintype "passive"))
      (node (ref "RP7") (pin "1") (pinfunction "1_1") (pintype "passive"))
      (node (ref "RP7") (pin "2") (pinfunction "2_2") (pintype "passive"))
      (node (ref "RP7") (pin "3") (pinfunction "3_3") (pintype "passive"))
      (node (ref "RP7") (pin "4") (pinfunction "4_4") (pintype "passive"))
      (node (ref "S1") (pin "1") (pinfunction "1_1") (pintype "passive"))
      (node (ref "S1") (pin "3") (pinfunction "3_3") (pintype "passive"))
      (node (ref "U1") (pin "31") (pinfunction "EA/Vpp_31") (pintype "passive"))
      (node (ref "U1") (pin "40") (pinfunction "VCC_40") (pintype "passive"))
    )
    (net (code "83") (name "unconnected-(74HC154-~{Y}12-Pad14)") (class "Default")
      (node (ref "74HC154") (pin "14") (pinfunction "~{Y}12_14") (pintype "passive"))
    )
    (net (code "84") (name "unconnected-(74HC154-~{Y}13-Pad15)") (class "Default")
      (node (ref "74HC154") (pin "15") (pinfunction "~{Y}13_15") (pintype "passive"))
    )
    (net (code "85") (name "unconnected-(74HC154-~{Y}14-Pad16)") (class "Default")
      (node (ref "74HC154") (pin "16") (pinfunction "~{Y}14_16") (pintype "passive"))
    )
    (net (code "86") (name "unconnected-(74HC154-~{Y}15-Pad17)") (class "Default")
      (node (ref "74HC154") (pin "17") (pinfunction "~{Y}15_17") (pintype "passive"))
    )
    (net (code "87") (name "unconnected-(CH1-CTS#-Pad9)") (class "Default")
      (node (ref "CH1") (pin "9") (pinfunction "CTS#_9") (pintype "passive"))
    )
    (net (code "88") (name "unconnected-(CH1-DCD#-Pad12)") (class "Default")
      (node (ref "CH1") (pin "12") (pinfunction "DCD#_12") (pintype "passive"))
    )
    (net (code "89") (name "unconnected-(CH1-DSR#-Pad10)") (class "Default")
      (node (ref "CH1") (pin "10") (pinfunction "DSR#_10") (pintype "passive"))
    )
    (net (code "90") (name "unconnected-(CH1-R232-Pad15)") (class "Default")
      (node (ref "CH1") (pin "15") (pinfunction "R232_15") (pintype "passive"))
    )
    (net (code "91") (name "unconnected-(CH1-RI#-Pad11)") (class "Default")
      (node (ref "CH1") (pin "11") (pinfunction "RI#_11") (pintype "passive"))
    )
    (net (code "92") (name "unconnected-(RP5-Pad1)") (class "Default")
      (node (ref "RP5") (pin "1") (pinfunction "1_1") (pintype "passive"))
    )
    (net (code "93") (name "unconnected-(RP5-Pad2)") (class "Default")
      (node (ref "RP5") (pin "2") (pinfunction "2_2") (pintype "passive"))
    )
    (net (code "94") (name "unconnected-(RP5-Pad3)") (class "Default")
      (node (ref "RP5") (pin "3") (pinfunction "3_3") (pintype "passive"))
    )
    (net (code "95") (name "unconnected-(RP5-Pad4)") (class "Default")
      (node (ref "RP5") (pin "4") (pinfunction "4_4") (pintype "passive"))
    )
    (net (code "96") (name "unconnected-(S2-Pad1)") (class "Default")
      (node (ref "S2") (pin "1") (pinfunction "1_1") (pintype "passive"))
    )
    (net (code "97") (name "unconnected-(S2-Pad4)") (class "Default")
      (node (ref "S2") (pin "4") (pinfunction "4_4") (pintype "passive"))
    )
    (net (code "98") (name "unconnected-(S2-Pad5)") (class "Default")
      (node (ref "S2") (pin "5") (pinfunction "5_5") (pintype "passive"))
    )
    (net (code "99") (name "unconnected-(S2-Pad6)") (class "Default")
      (node (ref "S2") (pin "6") (pinfunction "6_6") (pintype "passive"))
    )
    (net (code "100") (name "unconnected-(U1-ALE{slash}PROG-Pad30)") (class "Default")
      (node (ref "U1") (pin "30") (pinfunction "ALE/PROG_30") (pintype "passive"))
    )
    (net (code "101") (name "unconnected-(U1-PSEN-Pad29)") (class "Default")
      (node (ref "U1") (pin "29") (pinfunction "PSEN_29") (pintype "passive"))
    )
  )
)
